# ST_LINK.net
KiCad netlist of a schematic drawn in Altium Designer
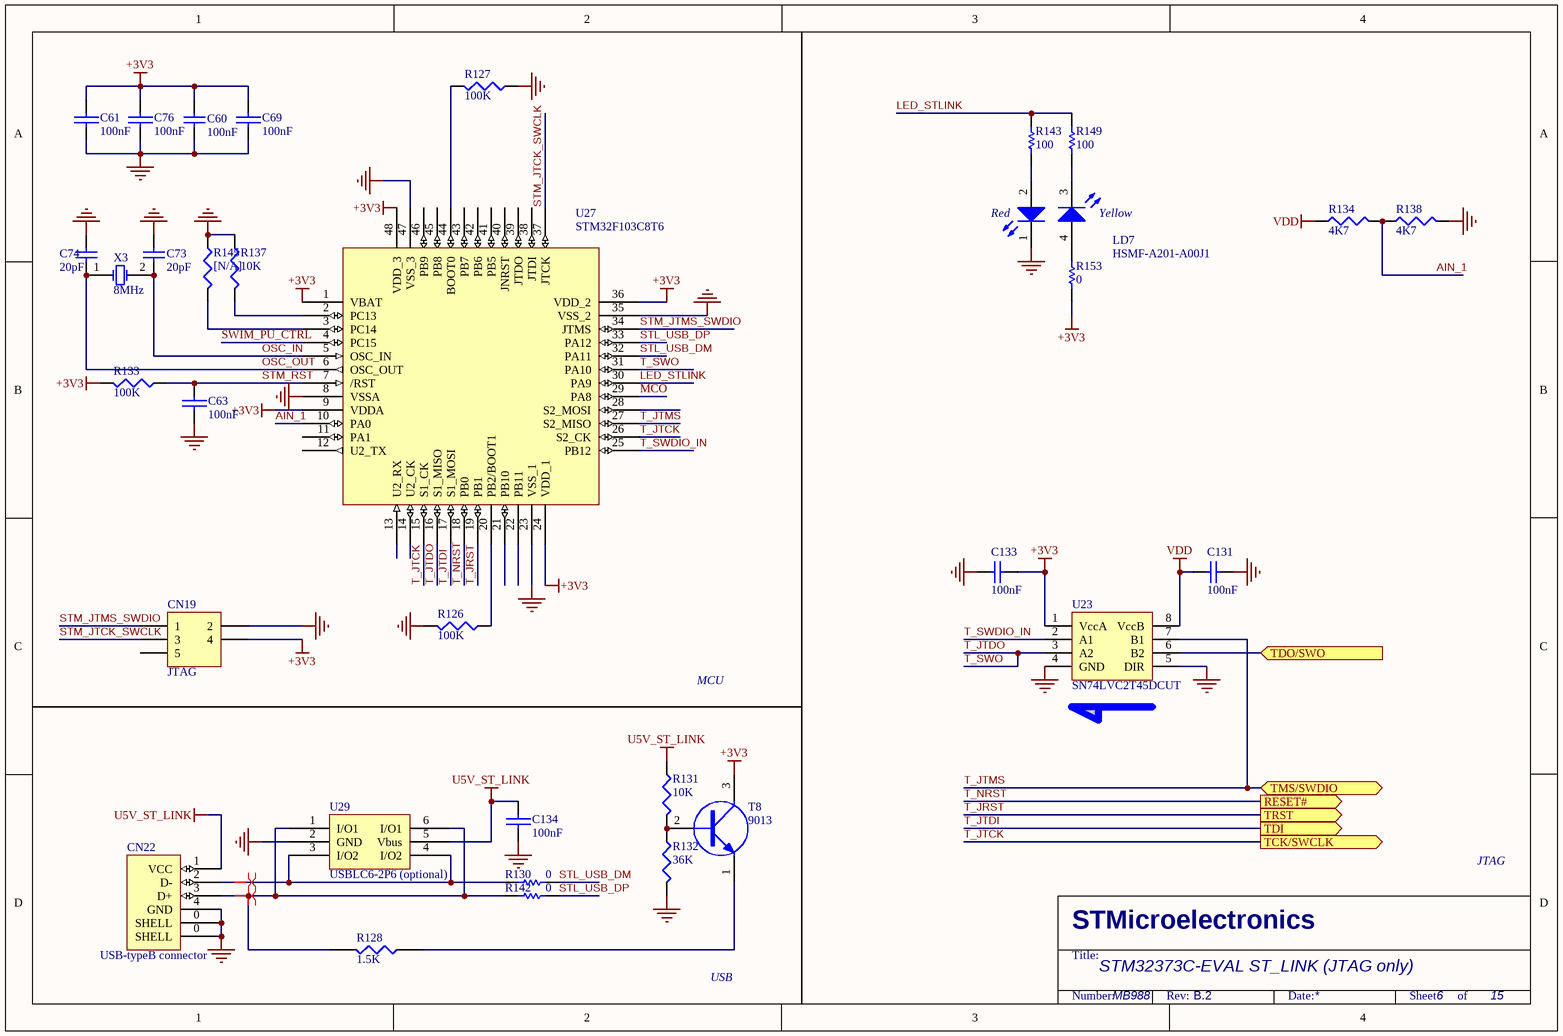
[diagram p0: ST_LINK.SCHDOC]

(export (version "E")
  (design (tool "Eeschema 10.0.6"))
  (components
    (comp (ref "C60")
      (value "100nF")
      (footprint "0603C")
      (description "Capacitor")
      (fields (field (name "PUBLISHER") "Altium Limited"))
      (libsource (lib "*") (part "Cap"))
    )
    (comp (ref "C61") (value "100nF") (footprint "0603C") (libsource (lib "*") (part "CAP")))
    (comp (ref "C63") (value "100nF") (footprint "0603C") (libsource (lib "*") (part "CAP")))
    (comp (ref "C69") (value "100nF") (footprint "0603C") (libsource (lib "*") (part "CAP")))
    (comp (ref "C73")
      (value "20pF")
      (footprint "0603R")
      (description "Capacitor")
      (fields (field (name "Comment") "Cap") (field (name "PUBLISHER") "Altium Limited"))
      (libsource (lib "*") (part "Cap"))
    )
    (comp (ref "C74")
      (value "20pF")
      (footprint "0603R")
      (description "Capacitor")
      (fields (field (name "Comment") "Cap") (field (name "PUBLISHER") "Altium Limited"))
      (libsource (lib "*") (part "Cap"))
    )
    (comp (ref "C76") (value "100nF") (footprint "0603C") (libsource (lib "*") (part "CAP")))
    (comp (ref "C131")
      (value "100nF")
      (footprint "0603C")
      (description "Capacitor")
      (fields (field (name "PUBLISHER") "Altium Limited"))
      (libsource (lib "Miscellaneous Devices") (part "CAP"))
    )
    (comp (ref "C133")
      (value "100nF")
      (footprint "0603C")
      (description "Capacitor")
      (fields (field (name "PUBLISHER") "Altium Limited"))
      (libsource (lib "Miscellaneous Devices") (part "CAP"))
    )
    (comp (ref "C134")
      (value "100nF")
      (footprint "0603C")
      (description "Capacitor")
      (libsource (lib "") (part "CAP_1"))
    )
    (comp (ref "CN19")
      (value "JTAG")
      (footprint "2*3P")
      (description "Header, 3-Pin, Dual row")
      (fields (field (name "PUBLISHER") "Altium Limited"))
      (libsource (lib "Miscellaneous Connectors") (part "Header 3X2"))
    )
    (comp (ref "CN22")
      (value "USB-typeB connector")
      (footprint "USB-B")
      (libsource (lib "*") (part "USB-typeB connector"))
    )
    (comp (ref "LD7")
      (value "HSMF-A201-A00J1")
      (footprint "LED2-28*32")
      (libsource (lib "MB819") (part "HSMF-A201-A00J1"))
    )
    (comp (ref "R126") (value "100K") (footprint "0603R") (libsource (lib "*") (part "RES1")))
    (comp (ref "R127") (value "100K") (footprint "0603R") (libsource (lib "*") (part "RES1")))
    (comp (ref "R128") (value "1.5K") (footprint "0603R") (libsource (lib "") (part "RES1_1")))
    (comp (ref "R130")
      (value "0")
      (footprint "0603R")
      (description "Resistor")
      (fields (field (name "PUBLISHER") "Altium Limited"))
      (libsource (lib "Miscellaneous Devices") (part "Res1"))
    )
    (comp (ref "R131") (value "10K") (footprint "0603R") (libsource (lib "*") (part "R")))
    (comp (ref "R132") (value "36K") (footprint "0603R") (libsource (lib "*") (part "R")))
    (comp (ref "R133") (value "100K") (footprint "0603R") (libsource (lib "*") (part "RES1")))
    (comp (ref "R134") (value "4K7") (footprint "0603R") (libsource (lib "*") (part "RES1")))
    (comp (ref "R137") (value "10K") (footprint "0603R") (libsource (lib "*") (part "R")))
    (comp (ref "R138") (value "4K7") (footprint "0603R") (libsource (lib "*") (part "RES1")))
    (comp (ref "R142")
      (value "0")
      (footprint "0603R")
      (description "Resistor")
      (fields (field (name "PUBLISHER") "Altium Limited"))
      (libsource (lib "Miscellaneous Devices") (part "Res1"))
    )
    (comp (ref "R143")
      (value "100")
      (footprint "0603R")
      (description "Resistor")
      (fields (field (name "PUBLISHER") "Altium Limited"))
      (libsource (lib "Miscellaneous Devices") (part "Res1"))
    )
    (comp (ref "R145") (value "[N/A]") (footprint "0603R") (libsource (lib "*") (part "R")))
    (comp (ref "R149")
      (value "100")
      (footprint "0603R")
      (description "Resistor")
      (fields (field (name "PUBLISHER") "Altium Limited"))
      (libsource (lib "Miscellaneous Devices") (part "Res1"))
    )
    (comp (ref "R153")
      (value "0")
      (footprint "0603R")
      (description "Resistor")
      (fields (field (name "PUBLISHER") "Altium Limited"))
      (libsource (lib "Miscellaneous Devices") (part "Res1"))
    )
    (comp (ref "T8") (value "9013") (footprint "SOT-23") (libsource (lib "*") (part "NPN")))
    (comp (ref "U23")
      (value "SN74LVC2T45DCUT")
      (footprint "VSSOP8")
      (libsource (lib "STLINK") (part "SN74LVC2T45DCUT"))
    )
    (comp (ref "U27")
      (value "STM32F103C8T6")
      (footprint "LQFP48")
      (libsource (lib "*") (part "STM32F10x(48pin)"))
    )
    (comp (ref "U29")
      (value "USBLC6-2P6 (optional)")
      (footprint "SOT-666")
      (libsource (lib "STR910_SCHLIB") (part "USBLC6-2"))
    )
    (comp (ref "X3")
      (value "8MHz")
      (footprint "SMT_XTAL")
      (description "Crystal Oscillator")
      (fields (field (name "PUBLISHER") "Altium Limited"))
      (libsource (lib "*") (part "XTAL"))
    )
  )
  (nets
    (net (code "1") (name "+3V3") (class "Default")
      (node (ref "C133") (pin "2") (pinfunction "2_2") (pintype "passive"))
      (node (ref "C60") (pin "1") (pinfunction "1_1") (pintype "passive"))
      (node (ref "C61") (pin "2") (pinfunction "2_2") (pintype "passive"))
      (node (ref "C69") (pin "2") (pinfunction "2_2") (pintype "passive"))
      (node (ref "C76") (pin "2") (pinfunction "2_2") (pintype "passive"))
      (node (ref "CN19") (pin "4") (pinfunction "4_4") (pintype "passive"))
      (node (ref "R133") (pin "2") (pinfunction "2_2") (pintype "passive"))
      (node (ref "R153") (pin "2") (pinfunction "2_2") (pintype "passive"))
      (node (ref "T8") (pin "3") (pinfunction "C_3") (pintype "passive"))
      (node (ref "U23") (pin "1") (pinfunction "VccA_1") (pintype "passive"))
      (node (ref "U27") (pin "1") (pinfunction "VBAT_1") (pintype "power_in"))
      (node (ref "U27") (pin "24") (pinfunction "VDD_1_24") (pintype "power_in"))
      (node (ref "U27") (pin "36") (pinfunction "VDD_2_36") (pintype "power_in"))
      (node (ref "U27") (pin "48") (pinfunction "VDD_3_48") (pintype "power_in"))
      (node (ref "U27") (pin "9") (pinfunction "VDDA_9") (pintype "power_in"))
    )
    (net (code "2") (name "/AIN_1") (class "Default")
      (node (ref "R134") (pin "2") (pinfunction "2_2") (pintype "passive"))
      (node (ref "R138") (pin "1") (pinfunction "1_1") (pintype "passive"))
      (node (ref "U27") (pin "10") (pinfunction "PA0_10") (pintype "bidirectional"))
    )
    (net (code "3") (name "/LED_STLINK") (class "Default")
      (node (ref "R143") (pin "1") (pinfunction "1_1") (pintype "passive"))
      (node (ref "R149") (pin "1") (pinfunction "1_1") (pintype "passive"))
      (node (ref "U27") (pin "30") (pinfunction "PA9_30") (pintype "bidirectional"))
    )
    (net (code "4") (name "/MCO") (class "Default")
      (node (ref "U27") (pin "29") (pinfunction "PA8_29") (pintype "bidirectional"))
    )
    (net (code "5") (name "/OSC_IN") (class "Default")
      (node (ref "C73") (pin "2") (pinfunction "2_2") (pintype "passive"))
      (node (ref "U27") (pin "5") (pinfunction "OSC_IN_5") (pintype "input"))
      (node (ref "X3") (pin "2") (pinfunction "OSC2_2") (pintype "passive"))
    )
    (net (code "6") (name "/OSC_OUT") (class "Default")
      (node (ref "C74") (pin "2") (pinfunction "2_2") (pintype "passive"))
      (node (ref "U27") (pin "6") (pinfunction "OSC_OUT_6") (pintype "output"))
      (node (ref "X3") (pin "1") (pinfunction "OSC1_1") (pintype "passive"))
    )
    (net (code "7") (name "/STL_USB_DM") (class "Default")
      (node (ref "R130") (pin "1") (pinfunction "1_1") (pintype "passive"))
      (node (ref "U27") (pin "32") (pinfunction "PA11_32") (pintype "bidirectional"))
    )
    (net (code "8") (name "/STL_USB_DP") (class "Default")
      (node (ref "R142") (pin "1") (pinfunction "1_1") (pintype "passive"))
      (node (ref "U27") (pin "33") (pinfunction "PA12_33") (pintype "bidirectional"))
    )
    (net (code "9") (name "/STM_JTCK_SWCLK") (class "Default")
      (node (ref "CN19") (pin "3") (pinfunction "3_3") (pintype "passive"))
      (node (ref "U27") (pin "37") (pinfunction "JTCK_37") (pintype "bidirectional"))
    )
    (net (code "10") (name "/STM_JTMS_SWDIO") (class "Default")
      (node (ref "CN19") (pin "1") (pinfunction "1_1") (pintype "passive"))
      (node (ref "U27") (pin "34") (pinfunction "JTMS_34") (pintype "bidirectional"))
    )
    (net (code "11") (name "/STM_RST") (class "Default")
      (node (ref "C63") (pin "2") (pinfunction "2_2") (pintype "passive"))
      (node (ref "R133") (pin "1") (pinfunction "1_1") (pintype "passive"))
      (node (ref "U27") (pin "7") (pinfunction "/RST_7") (pintype "input"))
    )
    (net (code "12") (name "/SWIM_PU_CTRL") (class "Default")
      (node (ref "U27") (pin "4") (pinfunction "PC15_4") (pintype "bidirectional"))
    )
    (net (code "13") (name "/TDO{slash}SWO") (class "Default")
      (node (ref "U23") (pin "6") (pinfunction "B2_6") (pintype "passive"))
    )
    (net (code "14") (name "/T_JRST") (class "Default")
      (node (ref "U27") (pin "19") (pinfunction "PB1_19") (pintype "bidirectional"))
    )
    (net (code "15") (name "/T_JTCK") (class "Default")
      (node (ref "U27") (pin "15") (pinfunction "S1_CK_15") (pintype "bidirectional"))
      (node (ref "U27") (pin "26") (pinfunction "S2_CK_26") (pintype "bidirectional"))
    )
    (net (code "16") (name "/T_JTDI") (class "Default")
      (node (ref "U27") (pin "17") (pinfunction "S1_MOSI_17") (pintype "bidirectional"))
    )
    (net (code "17") (name "/T_JTDO") (class "Default")
      (node (ref "U23") (pin "3") (pinfunction "A2_3") (pintype "passive"))
      (node (ref "U27") (pin "16") (pinfunction "S1_MISO_16") (pintype "bidirectional"))
      (node (ref "U27") (pin "31") (pinfunction "PA10_31") (pintype "bidirectional"))
    )
    (net (code "18") (name "/T_JTMS") (class "Default")
      (node (ref "U23") (pin "7") (pinfunction "B1_7") (pintype "passive"))
      (node (ref "U27") (pin "27") (pinfunction "S2_MISO_27") (pintype "bidirectional"))
    )
    (net (code "19") (name "/T_NRST") (class "Default")
      (node (ref "U27") (pin "18") (pinfunction "PB0_18") (pintype "bidirectional"))
    )
    (net (code "20") (name "/T_SWDIO_IN") (class "Default")
      (node (ref "U23") (pin "2") (pinfunction "A1_2") (pintype "passive"))
      (node (ref "U27") (pin "25") (pinfunction "PB12_25") (pintype "bidirectional"))
    )
    (net (code "21") (name "GND") (class "Default")
      (node (ref "C131") (pin "2") (pinfunction "2_2") (pintype "passive"))
      (node (ref "C133") (pin "1") (pinfunction "1_1") (pintype "passive"))
      (node (ref "C134") (pin "2") (pinfunction "2_2") (pintype "passive"))
      (node (ref "C60") (pin "2") (pinfunction "2_2") (pintype "passive"))
      (node (ref "C61") (pin "1") (pinfunction "1_1") (pintype "passive"))
      (node (ref "C63") (pin "1") (pinfunction "1_1") (pintype "passive"))
      (node (ref "C69") (pin "1") (pinfunction "1_1") (pintype "passive"))
      (node (ref "C73") (pin "1") (pinfunction "1_1") (pintype "passive"))
      (node (ref "C74") (pin "1") (pinfunction "1_1") (pintype "passive"))
      (node (ref "C76") (pin "1") (pinfunction "1_1") (pintype "passive"))
      (node (ref "CN19") (pin "2") (pinfunction "2_2") (pintype "passive"))
      (node (ref "CN22") (pin "0") (pinfunction "SHELL_0") (pintype "power_in"))
      (node (ref "CN22") (pin "4") (pinfunction "GND_4") (pintype "passive"))
      (node (ref "LD7") (pin "1") (pinfunction "RED_cathode_1") (pintype "passive"))
      (node (ref "R126") (pin "2") (pinfunction "2_2") (pintype "passive"))
      (node (ref "R127") (pin "1") (pinfunction "1_1") (pintype "passive"))
      (node (ref "R132") (pin "2") (pinfunction "2_2") (pintype "passive"))
      (node (ref "R137") (pin "1") (pinfunction "1_1") (pintype "passive"))
      (node (ref "R138") (pin "2") (pinfunction "2_2") (pintype "passive"))
      (node (ref "R145") (pin "1") (pinfunction "1_1") (pintype "passive"))
      (node (ref "U23") (pin "4") (pinfunction "GND_4") (pintype "passive"))
      (node (ref "U23") (pin "5") (pinfunction "DIR_5") (pintype "passive"))
      (node (ref "U27") (pin "23") (pinfunction "VSS_1_23") (pintype "passive"))
      (node (ref "U27") (pin "35") (pinfunction "VSS_2_35") (pintype "passive"))
      (node (ref "U27") (pin "47") (pinfunction "VSS_3_47") (pintype "passive"))
      (node (ref "U27") (pin "8") (pinfunction "VSSA_8") (pintype "passive"))
      (node (ref "U29") (pin "2") (pinfunction "GND_2") (pintype "passive"))
    )
    (net (code "22") (name "Net-(CN22-D+)") (class "Default")
      (node (ref "CN22") (pin "3") (pinfunction "D+_3") (pintype "bidirectional"))
      (node (ref "R128") (pin "2") (pinfunction "2_2") (pintype "passive"))
      (node (ref "R142") (pin "2") (pinfunction "2_2") (pintype "passive"))
      (node (ref "U29") (pin "1") (pinfunction "I/O1_1") (pintype "passive"))
      (node (ref "U29") (pin "6") (pinfunction "I/O1_6") (pintype "passive"))
    )
    (net (code "23") (name "Net-(CN22-D-)") (class "Default")
      (node (ref "CN22") (pin "2") (pinfunction "D-_2") (pintype "bidirectional"))
      (node (ref "R130") (pin "2") (pinfunction "2_2") (pintype "passive"))
      (node (ref "U29") (pin "3") (pinfunction "I/O2_3") (pintype "passive"))
      (node (ref "U29") (pin "4") (pinfunction "I/O2_4") (pintype "passive"))
    )
    (net (code "24") (name "Net-(LD7-Red_anode)") (class "Default")
      (node (ref "LD7") (pin "2") (pinfunction "Red_anode_2") (pintype "passive"))
      (node (ref "R143") (pin "2") (pinfunction "2_2") (pintype "passive"))
    )
    (net (code "25") (name "Net-(LD7-YellowGreen_anode)") (class "Default")
      (node (ref "LD7") (pin "4") (pinfunction "YellowGreen_anode_4") (pintype "passive"))
      (node (ref "R153") (pin "1") (pinfunction "1_1") (pintype "passive"))
    )
    (net (code "26") (name "Net-(LD7-YellowGreen_cathode)") (class "Default")
      (node (ref "LD7") (pin "3") (pinfunction "YellowGreen_cathode_3") (pintype "passive"))
      (node (ref "R149") (pin "2") (pinfunction "2_2") (pintype "passive"))
    )
    (net (code "27") (name "Net-(T8-B)") (class "Default")
      (node (ref "R131") (pin "2") (pinfunction "2_2") (pintype "passive"))
      (node (ref "R132") (pin "1") (pinfunction "1_1") (pintype "passive"))
      (node (ref "T8") (pin "2") (pinfunction "B_2") (pintype "passive"))
    )
    (net (code "28") (name "Net-(T8-E)") (class "Default")
      (node (ref "R128") (pin "1") (pinfunction "1_1") (pintype "passive"))
      (node (ref "T8") (pin "1") (pinfunction "E_1") (pintype "passive"))
    )
    (net (code "29") (name "Net-(U27-BOOT0)") (class "Default")
      (node (ref "R127") (pin "2") (pinfunction "2_2") (pintype "passive"))
      (node (ref "U27") (pin "44") (pinfunction "BOOT0_44") (pintype "bidirectional"))
    )
    (net (code "30") (name "Net-(U27-PB2{slash}BOOT1)") (class "Default")
      (node (ref "R126") (pin "1") (pinfunction "1_1") (pintype "passive"))
      (node (ref "U27") (pin "20") (pinfunction "PB2/BOOT1_20") (pintype "passive"))
    )
    (net (code "31") (name "Net-(U27-PC13)") (class "Default")
      (node (ref "R137") (pin "2") (pinfunction "2_2") (pintype "passive"))
      (node (ref "U27") (pin "2") (pinfunction "PC13_2") (pintype "bidirectional"))
    )
    (net (code "32") (name "Net-(U27-PC14)") (class "Default")
      (node (ref "R145") (pin "2") (pinfunction "2_2") (pintype "passive"))
      (node (ref "U27") (pin "3") (pinfunction "PC14_3") (pintype "bidirectional"))
    )
    (net (code "33") (name "U5V_ST_LINK") (class "Default")
      (node (ref "C134") (pin "1") (pinfunction "1_1") (pintype "passive"))
      (node (ref "CN22") (pin "1") (pinfunction "VCC_1") (pintype "bidirectional"))
      (node (ref "R131") (pin "1") (pinfunction "1_1") (pintype "passive"))
      (node (ref "U29") (pin "5") (pinfunction "Vbus_5") (pintype "passive"))
    )
    (net (code "34") (name "VDD") (class "Default")
      (node (ref "C131") (pin "1") (pinfunction "1_1") (pintype "passive"))
      (node (ref "R134") (pin "1") (pinfunction "1_1") (pintype "passive"))
      (node (ref "U23") (pin "8") (pinfunction "VccB_8") (pintype "passive"))
    )
    (net (code "35") (name "unconnected-(CN19-Pad5)") (class "Default")
      (node (ref "CN19") (pin "5") (pinfunction "5_5") (pintype "passive"))
    )
    (net (code "36") (name "unconnected-(U27-JNRST-Pad40)") (class "Default")
      (node (ref "U27") (pin "40") (pinfunction "JNRST_40") (pintype "bidirectional"))
    )
    (net (code "37") (name "unconnected-(U27-JTDI-Pad38)") (class "Default")
      (node (ref "U27") (pin "38") (pinfunction "JTDI_38") (pintype "bidirectional"))
    )
    (net (code "38") (name "unconnected-(U27-JTDO-Pad39)") (class "Default")
      (node (ref "U27") (pin "39") (pinfunction "JTDO_39") (pintype "bidirectional"))
    )
    (net (code "39") (name "unconnected-(U27-PA1-Pad11)") (class "Default")
      (node (ref "U27") (pin "11") (pinfunction "PA1_11") (pintype "bidirectional"))
    )
    (net (code "40") (name "unconnected-(U27-PB5-Pad41)") (class "Default")
      (node (ref "U27") (pin "41") (pinfunction "PB5_41") (pintype "bidirectional"))
    )
    (net (code "41") (name "unconnected-(U27-PB6-Pad42)") (class "Default")
      (node (ref "U27") (pin "42") (pinfunction "PB6_42") (pintype "bidirectional"))
    )
    (net (code "42") (name "unconnected-(U27-PB7-Pad43)") (class "Default")
      (node (ref "U27") (pin "43") (pinfunction "PB7_43") (pintype "bidirectional"))
    )
    (net (code "43") (name "unconnected-(U27-PB8-Pad45)") (class "Default")
      (node (ref "U27") (pin "45") (pinfunction "PB8_45") (pintype "bidirectional"))
    )
    (net (code "44") (name "unconnected-(U27-PB9-Pad46)") (class "Default")
      (node (ref "U27") (pin "46") (pinfunction "PB9_46") (pintype "bidirectional"))
    )
    (net (code "45") (name "unconnected-(U27-PB10-Pad21)") (class "Default")
      (node (ref "U27") (pin "21") (pinfunction "PB10_21") (pintype "bidirectional"))
    )
    (net (code "46") (name "unconnected-(U27-PB11-Pad22)") (class "Default")
      (node (ref "U27") (pin "22") (pinfunction "PB11_22") (pintype "passive"))
    )
    (net (code "47") (name "unconnected-(U27-S2_MOSI-Pad28)") (class "Default")
      (node (ref "U27") (pin "28") (pinfunction "S2_MOSI_28") (pintype "bidirectional"))
    )
    (net (code "48") (name "unconnected-(U27-U2_CK-Pad14)") (class "Default")
      (node (ref "U27") (pin "14") (pinfunction "U2_CK_14") (pintype "bidirectional"))
    )
    (net (code "49") (name "unconnected-(U27-U2_RX-Pad13)") (class "Default")
      (node (ref "U27") (pin "13") (pinfunction "U2_RX_13") (pintype "input"))
    )
    (net (code "50") (name "unconnected-(U27-U2_TX-Pad12)") (class "Default")
      (node (ref "U27") (pin "12") (pinfunction "U2_TX_12") (pintype "output"))
    )
  )
)
